# design.net
KiCad netlist of a schematic drawn in Altium Designer
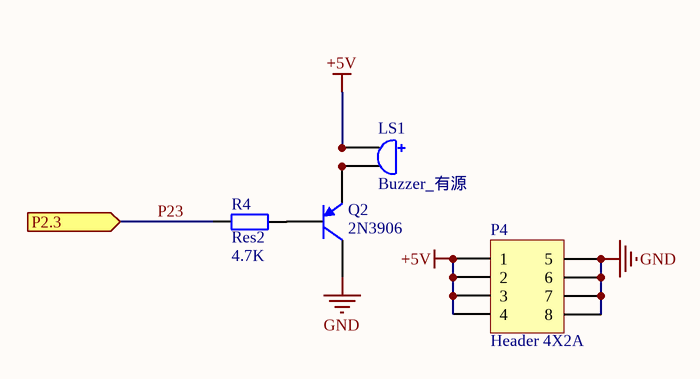
[diagram p0: 蜂鸣器.SchDoc]

(export (version "E")
  (design (tool "Eeschema 10.0.6"))
  (components
    (comp (ref "LS1")
      (value "Buzzer_有源")
      (footprint "51开发板封装库_W:DIP6.6_2P")
      (libsource (lib "51开发板原理图库") (part "Buzzer_有源"))
    )
    (comp (ref "P4")
      (value "Header 4X2A")
      (footprint "HDR2X4_CEN")
      (description "Header, 4-Pin, Dual row")
      (fields (field (name "PUBLISHER") "Altium Limited"))
      (libsource (lib "Miscellaneous Connectors") (part "Header 4X2A"))
    )
    (comp (ref "Q2")
      (value "2N3906")
      (footprint "TO-92A")
      (description "PNP General Purpose Amplifier")
      (fields (field (name "PUBLISHER") "Altium Limited"))
      (libsource (lib "Miscellaneous Devices") (part "2N3906"))
    )
    (comp (ref "R4")
      (value "Res2")
      (footprint "AXIAL-0.4")
      (description "Resistor")
      (fields (field (name "ALTIUM_VALUE") "4.7K") (field (name "PUBLISHER") "Altium Limited"))
      (libsource (lib "Miscellaneous Devices") (part "Res2"))
    )
  )
  (nets
    (net (code "1") (name "+5V") (class "Default")
      (node (ref "LS1") (pin "1") (pinfunction "1_1") (pintype "passive"))
      (node (ref "P4") (pin "1") (pinfunction "1_1") (pintype "passive"))
      (node (ref "P4") (pin "2") (pinfunction "2_2") (pintype "passive"))
      (node (ref "P4") (pin "3") (pinfunction "3_3") (pintype "passive"))
      (node (ref "P4") (pin "4") (pinfunction "4_4") (pintype "passive"))
    )
    (net (code "2") (name "/P23") (class "Default")
      (node (ref "R4") (pin "1") (pinfunction "1_1") (pintype "passive"))
    )
    (net (code "3") (name "GND") (class "Default")
      (node (ref "P4") (pin "5") (pinfunction "5_5") (pintype "passive"))
      (node (ref "P4") (pin "6") (pinfunction "6_6") (pintype "passive"))
      (node (ref "P4") (pin "7") (pinfunction "7_7") (pintype "passive"))
      (node (ref "P4") (pin "8") (pinfunction "8_8") (pintype "passive"))
      (node (ref "Q2") (pin "3") (pinfunction "C_3") (pintype "passive"))
    )
    (net (code "4") (name "Net-(Q2-B)") (class "Default")
      (node (ref "Q2") (pin "2") (pinfunction "B_2") (pintype "passive"))
      (node (ref "R4") (pin "2") (pinfunction "2_2") (pintype "passive"))
    )
    (net (code "5") (name "Net-(Q2-E)") (class "Default")
      (node (ref "LS1") (pin "2") (pinfunction "2_2") (pintype "passive"))
      (node (ref "Q2") (pin "1") (pinfunction "E_1") (pintype "passive"))
    )
  )
)
